# design.net
KiCad netlist of a schematic drawn in Altium Designer
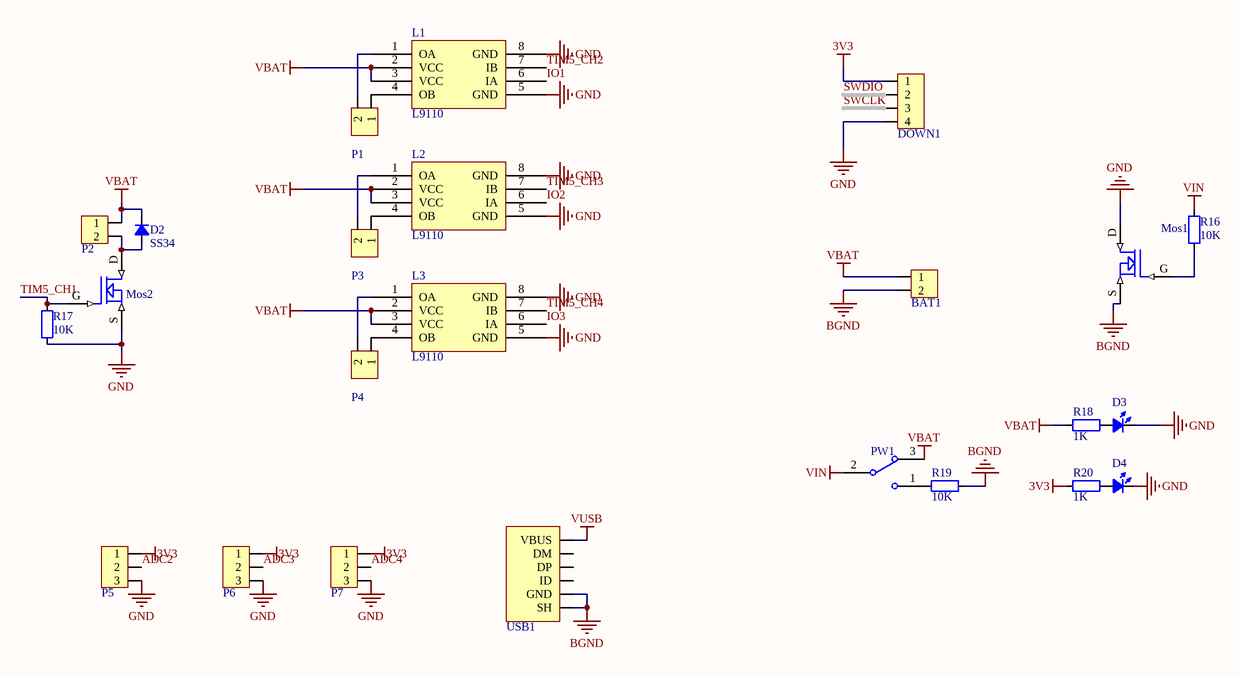
[diagram p0: 接口.SchDoc]

(export (version "E")
  (design (tool "Eeschema 10.0.6"))
  (components
    (comp (ref "BAT1")
      (value "HDR1x2_2.54")
      (footprint "PCB_ConnectorHDR:HDR1X2_2.54_90")
      (description "Header")
      (libsource (lib "") (part "HDR1x2_2.54_1"))
    )
    (comp (ref "D2")
      (value "SS34")
      (footprint "PCB_ActiveDIO:DO-214AC")
      (description "Diode")
      (fields (field (name "Comment") "Diode_SMA"))
      (libsource (lib "SCH_Active") (part "Diode_SMA"))
    )
    (comp (ref "D3")
      (value "LED_0805")
      (footprint "PCB_ActiveLED:LED_0805_YELLOW")
      (description "LED")
      (libsource (lib "SCH_Active") (part "LED_0805"))
    )
    (comp (ref "D4")
      (value "LED_0805")
      (footprint "PCB_ActiveLED:LED_0805_YELLOW")
      (description "LED")
      (libsource (lib "SCH_Active") (part "LED_0805"))
    )
    (comp (ref "DOWN1")
      (value "HDR1x4_2.54")
      (footprint "PCB_ConnectorHDR:HDR1X4_2.54_180")
      (description "Header")
      (libsource (lib "SCH_ConnectorHDR") (part "HDR1x4_2.54"))
    )
    (comp (ref "L1")
      (value "L9110")
      (footprint "SOP_E150_8")
      (libsource (lib "K60-mainboard-v3.1") (part "L9110"))
    )
    (comp (ref "L2")
      (value "L9110")
      (footprint "SOP_E150_8")
      (libsource (lib "K60-mainboard-v3.1") (part "L9110"))
    )
    (comp (ref "L3")
      (value "L9110")
      (footprint "SOP_E150_8")
      (libsource (lib "K60-mainboard-v3.1") (part "L9110"))
    )
    (comp (ref "Mos1")
      (value "MOSFET N")
      (footprint "Nmos_SOT23")
      (description "MOS SOT23")
      (libsource (lib "SCH_Active") (part "MOSFET N"))
    )
    (comp (ref "Mos2")
      (value "MOSFET N")
      (footprint "Nmos_SOT23")
      (description "MOS SOT23")
      (libsource (lib "SCH_Active") (part "MOSFET N"))
    )
    (comp (ref "P1")
      (value "HDR1x2_2.54")
      (footprint "PCB_ConnectorHDR:HDR1X2_2.54_180")
      (description "Header")
      (libsource (lib "SCH_ConnectorHDR") (part "HDR1x2_2.54"))
    )
    (comp (ref "P2")
      (value "HDR1x2_2.54")
      (footprint "PCB_ConnectorHDR:HDR1X2_2.54_180")
      (description "Header")
      (libsource (lib "SCH_ConnectorHDR") (part "HDR1x2_2.54T"))
    )
    (comp (ref "P3")
      (value "HDR1x2_2.54")
      (footprint "PCB_ConnectorHDR:HDR1X2_2.54_180")
      (description "Header")
      (libsource (lib "SCH_ConnectorHDR") (part "HDR1x2_2.54"))
    )
    (comp (ref "P4")
      (value "HDR1x2_2.54")
      (footprint "PCB_ConnectorHDR:HDR1X2_2.54_180")
      (description "Header")
      (libsource (lib "SCH_ConnectorHDR") (part "HDR1x2_2.54"))
    )
    (comp (ref "P5")
      (value "HDR1x3_2.54")
      (footprint "PCB_ConnectorHDR:HDR1X3_2.54_180")
      (description "Header")
      (libsource (lib "SCH_ConnectorHDR") (part "HDR1x3_2.54T"))
    )
    (comp (ref "P6")
      (value "HDR1x3_2.54")
      (footprint "PCB_ConnectorHDR:HDR1X3_2.54_180")
      (description "Header")
      (libsource (lib "SCH_ConnectorHDR") (part "HDR1x3_2.54T"))
    )
    (comp (ref "P7")
      (value "HDR1x3_2.54")
      (footprint "PCB_ConnectorHDR:HDR1X3_2.54_180")
      (description "Header")
      (libsource (lib "SCH_ConnectorHDR") (part "HDR1x3_2.54T"))
    )
    (comp (ref "PW1")
      (value "SwitchSPDT_2.8x6.6_90")
      (footprint "PCB_Switch:SwitchSPDT_2.8X6.6_90")
      (description "Switch")
      (libsource (lib "SCH_Switch") (part "SwitchSPDT_2.8x6.6_90"))
    )
    (comp (ref "R16")
      (value "10K")
      (footprint "PCB_PassiveRes:RES_0603")
      (description "Resistor")
      (fields (field (name "Comment") "Res_0603"))
      (libsource (lib "") (part "Res_0603_1"))
    )
    (comp (ref "R17")
      (value "10K")
      (footprint "PCB_PassiveRes:RES_0603")
      (description "Resistor")
      (fields (field (name "Comment") "Res_0603"))
      (libsource (lib "") (part "Res_0603_1"))
    )
    (comp (ref "R18")
      (value "1K")
      (footprint "PCB_PassiveRes:RES_0603")
      (description "Resistor")
      (fields (field (name "Comment") "Res_0603"))
      (libsource (lib "SCH_Passive") (part "Res_0603"))
    )
    (comp (ref "R19")
      (value "10K")
      (footprint "PCB_PassiveRes:RES_0603")
      (description "Resistor")
      (fields (field (name "Comment") "Res_0603"))
      (libsource (lib "SCH_Passive") (part "Res_0603"))
    )
    (comp (ref "R20")
      (value "1K")
      (footprint "PCB_PassiveRes:RES_0603")
      (description "Resistor")
      (fields (field (name "Comment") "Res_0603"))
      (libsource (lib "SCH_Passive") (part "Res_0603"))
    )
    (comp (ref "USB1")
      (value "USB_Micro")
      (footprint "PCB_USB:USB_Micro-AB")
      (description "USB")
      (libsource (lib "SCH_USB") (part "USB_Micro"))
    )
  )
  (nets
    (net (code "1") (name "/ADC2") (class "Default")
      (node (ref "P5") (pin "2") (pinfunction "2_2") (pintype "passive"))
    )
    (net (code "2") (name "/ADC3") (class "Default")
      (node (ref "P6") (pin "2") (pinfunction "2_2") (pintype "passive"))
    )
    (net (code "3") (name "/ADC4") (class "Default")
      (node (ref "P7") (pin "2") (pinfunction "2_2") (pintype "passive"))
    )
    (net (code "4") (name "/IO1") (class "Default")
      (node (ref "L1") (pin "6") (pinfunction "IA_6") (pintype "passive"))
    )
    (net (code "5") (name "/IO2") (class "Default")
      (node (ref "L2") (pin "6") (pinfunction "IA_6") (pintype "passive"))
    )
    (net (code "6") (name "/IO3") (class "Default")
      (node (ref "L3") (pin "6") (pinfunction "IA_6") (pintype "passive"))
    )
    (net (code "7") (name "/SWCLK") (class "Default")
      (node (ref "DOWN1") (pin "3") (pinfunction "3_3") (pintype "passive"))
    )
    (net (code "8") (name "/SWDIO") (class "Default")
      (node (ref "DOWN1") (pin "2") (pinfunction "2_2") (pintype "passive"))
    )
    (net (code "9") (name "/TIM5_CH1") (class "Default")
      (node (ref "Mos2") (pin "G") (pinfunction "G_G") (pintype "input"))
      (node (ref "R17") (pin "2") (pinfunction "2_2") (pintype "passive"))
    )
    (net (code "10") (name "/TIM5_CH2") (class "Default")
      (node (ref "L1") (pin "7") (pinfunction "IB_7") (pintype "passive"))
    )
    (net (code "11") (name "/TIM5_CH3") (class "Default")
      (node (ref "L2") (pin "7") (pinfunction "IB_7") (pintype "passive"))
    )
    (net (code "12") (name "/TIM5_CH4") (class "Default")
      (node (ref "L3") (pin "7") (pinfunction "IB_7") (pintype "passive"))
    )
    (net (code "13") (name "3V3") (class "Default")
      (node (ref "DOWN1") (pin "1") (pinfunction "1_1") (pintype "passive"))
      (node (ref "P5") (pin "1") (pinfunction "1_1") (pintype "passive"))
      (node (ref "P6") (pin "1") (pinfunction "1_1") (pintype "passive"))
      (node (ref "P7") (pin "1") (pinfunction "1_1") (pintype "passive"))
      (node (ref "R20") (pin "1") (pinfunction "1_1") (pintype "passive"))
    )
    (net (code "14") (name "BGND") (class "Default")
      (node (ref "BAT1") (pin "2") (pinfunction "2_2") (pintype "passive"))
      (node (ref "Mos1") (pin "S") (pinfunction "S_S") (pintype "input"))
      (node (ref "R19") (pin "2") (pinfunction "2_2") (pintype "passive"))
      (node (ref "USB1") (pin "0") (pinfunction "SH_0") (pintype "passive"))
      (node (ref "USB1") (pin "5") (pinfunction "GND_5") (pintype "passive"))
    )
    (net (code "15") (name "GND") (class "Default")
      (node (ref "D3") (pin "2") (pinfunction "K_2") (pintype "passive"))
      (node (ref "D4") (pin "2") (pinfunction "K_2") (pintype "passive"))
      (node (ref "DOWN1") (pin "4") (pinfunction "4_4") (pintype "passive"))
      (node (ref "L1") (pin "5") (pinfunction "GND_5") (pintype "passive"))
      (node (ref "L1") (pin "8") (pinfunction "GND_8") (pintype "passive"))
      (node (ref "L2") (pin "5") (pinfunction "GND_5") (pintype "passive"))
      (node (ref "L2") (pin "8") (pinfunction "GND_8") (pintype "passive"))
      (node (ref "L3") (pin "5") (pinfunction "GND_5") (pintype "passive"))
      (node (ref "L3") (pin "8") (pinfunction "GND_8") (pintype "passive"))
      (node (ref "Mos1") (pin "D") (pinfunction "D_D") (pintype "input"))
      (node (ref "Mos2") (pin "S") (pinfunction "S_S") (pintype "input"))
      (node (ref "P5") (pin "3") (pinfunction "3_3") (pintype "passive"))
      (node (ref "P6") (pin "3") (pinfunction "3_3") (pintype "passive"))
      (node (ref "P7") (pin "3") (pinfunction "3_3") (pintype "passive"))
      (node (ref "R17") (pin "1") (pinfunction "1_1") (pintype "passive"))
    )
    (net (code "16") (name "Net-(D2-A)") (class "Default")
      (node (ref "D2") (pin "1") (pinfunction "A_1") (pintype "passive"))
      (node (ref "Mos2") (pin "D") (pinfunction "D_D") (pintype "input"))
      (node (ref "P2") (pin "2") (pinfunction "2_2") (pintype "passive"))
    )
    (net (code "17") (name "Net-(D3-A)") (class "Default")
      (node (ref "D3") (pin "1") (pinfunction "A_1") (pintype "passive"))
      (node (ref "R18") (pin "2") (pinfunction "2_2") (pintype "passive"))
    )
    (net (code "18") (name "Net-(D4-A)") (class "Default")
      (node (ref "D4") (pin "1") (pinfunction "A_1") (pintype "passive"))
      (node (ref "R20") (pin "2") (pinfunction "2_2") (pintype "passive"))
    )
    (net (code "19") (name "Net-(L1-OA)") (class "Default")
      (node (ref "L1") (pin "1") (pinfunction "OA_1") (pintype "passive"))
      (node (ref "P1") (pin "2") (pinfunction "2_2") (pintype "passive"))
    )
    (net (code "20") (name "Net-(L1-OB)") (class "Default")
      (node (ref "L1") (pin "4") (pinfunction "OB_4") (pintype "passive"))
      (node (ref "P1") (pin "1") (pinfunction "1_1") (pintype "passive"))
    )
    (net (code "21") (name "Net-(L2-OA)") (class "Default")
      (node (ref "L2") (pin "1") (pinfunction "OA_1") (pintype "passive"))
      (node (ref "P3") (pin "2") (pinfunction "2_2") (pintype "passive"))
    )
    (net (code "22") (name "Net-(L2-OB)") (class "Default")
      (node (ref "L2") (pin "4") (pinfunction "OB_4") (pintype "passive"))
      (node (ref "P3") (pin "1") (pinfunction "1_1") (pintype "passive"))
    )
    (net (code "23") (name "Net-(L3-OA)") (class "Default")
      (node (ref "L3") (pin "1") (pinfunction "OA_1") (pintype "passive"))
      (node (ref "P4") (pin "2") (pinfunction "2_2") (pintype "passive"))
    )
    (net (code "24") (name "Net-(L3-OB)") (class "Default")
      (node (ref "L3") (pin "4") (pinfunction "OB_4") (pintype "passive"))
      (node (ref "P4") (pin "1") (pinfunction "1_1") (pintype "passive"))
    )
    (net (code "25") (name "Net-(Mos1-PadG)") (class "Default")
      (node (ref "Mos1") (pin "G") (pinfunction "G_G") (pintype "input"))
      (node (ref "R16") (pin "1") (pinfunction "1_1") (pintype "passive"))
    )
    (net (code "26") (name "Net-(PW1-Pad1)") (class "Default")
      (node (ref "PW1") (pin "1") (pinfunction "1_1") (pintype "passive"))
      (node (ref "R19") (pin "1") (pinfunction "1_1") (pintype "passive"))
    )
    (net (code "27") (name "VBAT") (class "Default")
      (node (ref "BAT1") (pin "1") (pinfunction "1_1") (pintype "passive"))
      (node (ref "D2") (pin "2") (pinfunction "K_2") (pintype "passive"))
      (node (ref "L1") (pin "2") (pinfunction "VCC_2") (pintype "passive"))
      (node (ref "L1") (pin "3") (pinfunction "VCC_3") (pintype "passive"))
      (node (ref "L2") (pin "2") (pinfunction "VCC_2") (pintype "passive"))
      (node (ref "L2") (pin "3") (pinfunction "VCC_3") (pintype "passive"))
      (node (ref "L3") (pin "2") (pinfunction "VCC_2") (pintype "passive"))
      (node (ref "L3") (pin "3") (pinfunction "VCC_3") (pintype "passive"))
      (node (ref "P2") (pin "1") (pinfunction "1_1") (pintype "passive"))
      (node (ref "PW1") (pin "3") (pinfunction "3_3") (pintype "passive"))
      (node (ref "R18") (pin "1") (pinfunction "1_1") (pintype "passive"))
    )
    (net (code "28") (name "VIN") (class "Default")
      (node (ref "PW1") (pin "2") (pinfunction "2_2") (pintype "passive"))
      (node (ref "R16") (pin "2") (pinfunction "2_2") (pintype "passive"))
    )
    (net (code "29") (name "VUSB") (class "Default")
      (node (ref "USB1") (pin "1") (pinfunction "VBUS_1") (pintype "passive"))
    )
    (net (code "30") (name "unconnected-(USB1-DM-Pad2)") (class "Default")
      (node (ref "USB1") (pin "2") (pinfunction "DM_2") (pintype "passive"))
    )
    (net (code "31") (name "unconnected-(USB1-DP-Pad3)") (class "Default")
      (node (ref "USB1") (pin "3") (pinfunction "DP_3") (pintype "passive"))
    )
    (net (code "32") (name "unconnected-(USB1-ID-Pad4)") (class "Default")
      (node (ref "USB1") (pin "4") (pinfunction "ID_4") (pintype "passive"))
    )
  )
)
